# CAN.net
KiCad netlist of a schematic drawn in Altium Designer
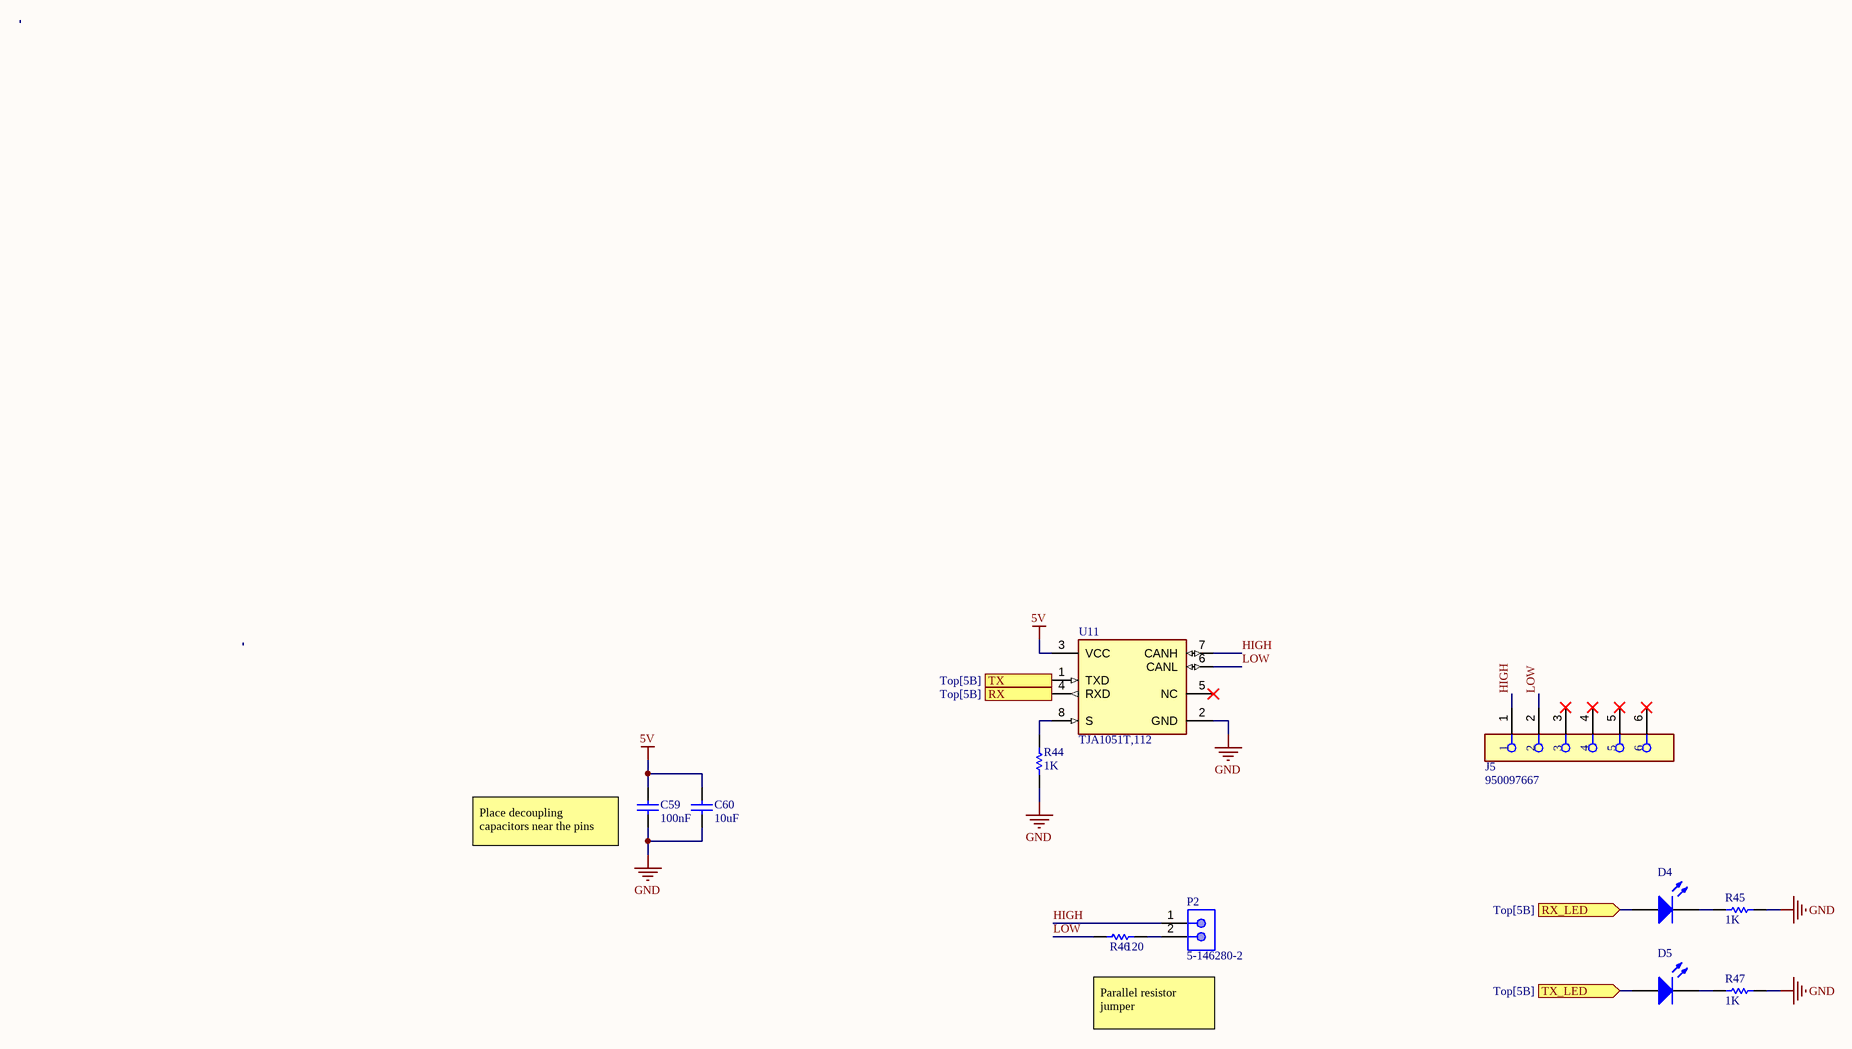
[diagram p0: CAN.SchDoc]

(export (version "E")
  (design (tool "Eeschema 10.0.6"))
  (components
    (comp (ref "C59")
      (value "100nF")
      (description "Capacitor")
      (libsource (lib "Simulation Generic Components") (part "Capacitor"))
    )
    (comp (ref "C60")
      (value "10uF")
      (description "Capacitor")
      (libsource (lib "Simulation Generic Components") (part "Capacitor"))
    )
    (comp (ref "D4")
      (value "Light-Emitting Diode")
      (libsource (lib "Simulation Generic Components") (part "LED"))
    )
    (comp (ref "D5")
      (value "Light-Emitting Diode")
      (libsource (lib "Simulation Generic Components") (part "LED"))
    )
    (comp (ref "J5")
      (value "950097667")
      (footprint "FP-950097667-MFG")
      (description "CONN MOD JACK 6P6C R/A UNSHLD")
      (fields
        (field (name "OCTOPART") "https://octopart.com/95009-7667-molex-24622630")
        (field (name "MANUFACTURER") "Molex")
      )
      (libsource (lib "Altium Content Vault") (part "340f86754993f25901839ab6d466df7"))
    )
    (comp (ref "P2")
      (value "5-146280-2")
      (footprint "TECO-5-146280-2_V")
      (fields (field (name "MANUFACTURER") "TE Connectivity"))
      (libsource (lib "Altium Content Vault") (part "CN-1P-M-R2"))
    )
    (comp (ref "R44")
      (value "1K")
      (description "Resistor")
      (libsource (lib "Simulation Generic Components") (part "Resistor"))
    )
    (comp (ref "R45")
      (value "1K")
      (description "Resistor")
      (libsource (lib "Simulation Generic Components") (part "Resistor"))
    )
    (comp (ref "R46")
      (value "120")
      (description "Resistor")
      (libsource (lib "Simulation Generic Components") (part "Resistor"))
    )
    (comp (ref "R47")
      (value "1K")
      (description "Resistor")
      (libsource (lib "Simulation Generic Components") (part "Resistor"))
    )
    (comp (ref "U11")
      (value "TJA1051T,112")
      (footprint "FP-SOT96-1-MFG")
      (description "IC TRANSCEIVER HALF 1/1 8SO")
      (fields
        (field (name "OCTOPART") "https://octopart.com/tja1051t%2C112-nxp+semiconductors-11542082")
        (field (name "MANUFACTURER") "NXP Semiconductors")
      )
      (libsource (lib "Altium Content Vault") (part "672a34478da9bd23e365b78d959257a"))
    )
  )
  (nets
    (net (code "1") (name "/HIGH") (class "Default")
      (node (ref "J5") (pin "1") (pinfunction "1_1") (pintype "passive"))
      (node (ref "P2") (pin "1") (pinfunction "1_1") (pintype "passive"))
      (node (ref "U11") (pin "7") (pinfunction "CANH_7") (pintype "bidirectional"))
    )
    (net (code "2") (name "/LOW") (class "Default")
      (node (ref "J5") (pin "2") (pinfunction "2_2") (pintype "passive"))
      (node (ref "R46") (pin "1") (pinfunction "1_1") (pintype "passive"))
      (node (ref "U11") (pin "6") (pinfunction "CANL_6") (pintype "bidirectional"))
    )
    (net (code "3") (name "/RX") (class "Default")
      (node (ref "U11") (pin "4") (pinfunction "RXD_4") (pintype "output"))
    )
    (net (code "4") (name "/RX_LED") (class "Default")
      (node (ref "D4") (pin "1") (pinfunction "A_1") (pintype "passive"))
    )
    (net (code "5") (name "/TX") (class "Default")
      (node (ref "U11") (pin "1") (pinfunction "TXD_1") (pintype "input"))
    )
    (net (code "6") (name "/TX_LED") (class "Default")
      (node (ref "D5") (pin "1") (pinfunction "A_1") (pintype "passive"))
    )
    (net (code "7") (name "5V") (class "Default")
      (node (ref "C59") (pin "2") (pinfunction "2_2") (pintype "passive"))
      (node (ref "C60") (pin "2") (pinfunction "2_2") (pintype "passive"))
      (node (ref "U11") (pin "3") (pinfunction "VCC_3") (pintype "power_in"))
    )
    (net (code "8") (name "GND") (class "Default")
      (node (ref "C59") (pin "1") (pinfunction "1_1") (pintype "passive"))
      (node (ref "C60") (pin "1") (pinfunction "1_1") (pintype "passive"))
      (node (ref "R44") (pin "1") (pinfunction "1_1") (pintype "passive"))
      (node (ref "R45") (pin "2") (pinfunction "2_2") (pintype "passive"))
      (node (ref "R47") (pin "2") (pinfunction "2_2") (pintype "passive"))
      (node (ref "U11") (pin "2") (pinfunction "GND_2") (pintype "power_in"))
    )
    (net (code "9") (name "Net-(D4-K)") (class "Default")
      (node (ref "D4") (pin "2") (pinfunction "K_2") (pintype "passive"))
      (node (ref "R45") (pin "1") (pinfunction "1_1") (pintype "passive"))
    )
    (net (code "10") (name "Net-(D5-K)") (class "Default")
      (node (ref "D5") (pin "2") (pinfunction "K_2") (pintype "passive"))
      (node (ref "R47") (pin "1") (pinfunction "1_1") (pintype "passive"))
    )
    (net (code "11") (name "Net-(P2-Pad2)") (class "Default")
      (node (ref "P2") (pin "2") (pinfunction "2_2") (pintype "passive"))
      (node (ref "R46") (pin "2") (pinfunction "2_2") (pintype "passive"))
    )
    (net (code "12") (name "Net-(U11-S)") (class "Default")
      (node (ref "R44") (pin "2") (pinfunction "2_2") (pintype "passive"))
      (node (ref "U11") (pin "8") (pinfunction "S_8") (pintype "input"))
    )
    (net (code "13") (name "unconnected-(J5-Pad3)") (class "Default")
      (node (ref "J5") (pin "3") (pinfunction "3_3") (pintype "passive+no_connect"))
    )
    (net (code "14") (name "unconnected-(J5-Pad4)") (class "Default")
      (node (ref "J5") (pin "4") (pinfunction "4_4") (pintype "passive+no_connect"))
    )
    (net (code "15") (name "unconnected-(J5-Pad5)") (class "Default")
      (node (ref "J5") (pin "5") (pinfunction "5_5") (pintype "passive+no_connect"))
    )
    (net (code "16") (name "unconnected-(J5-Pad6)") (class "Default")
      (node (ref "J5") (pin "6") (pinfunction "6_6") (pintype "passive+no_connect"))
    )
    (net (code "17") (name "unconnected-(U11-NC-Pad5)") (class "Default")
      (node (ref "U11") (pin "5") (pinfunction "NC_5") (pintype "passive+no_connect"))
    )
  )
)
